# LED_Matrix_3_3_Power.net
KiCad netlist of a schematic drawn in EAGLE
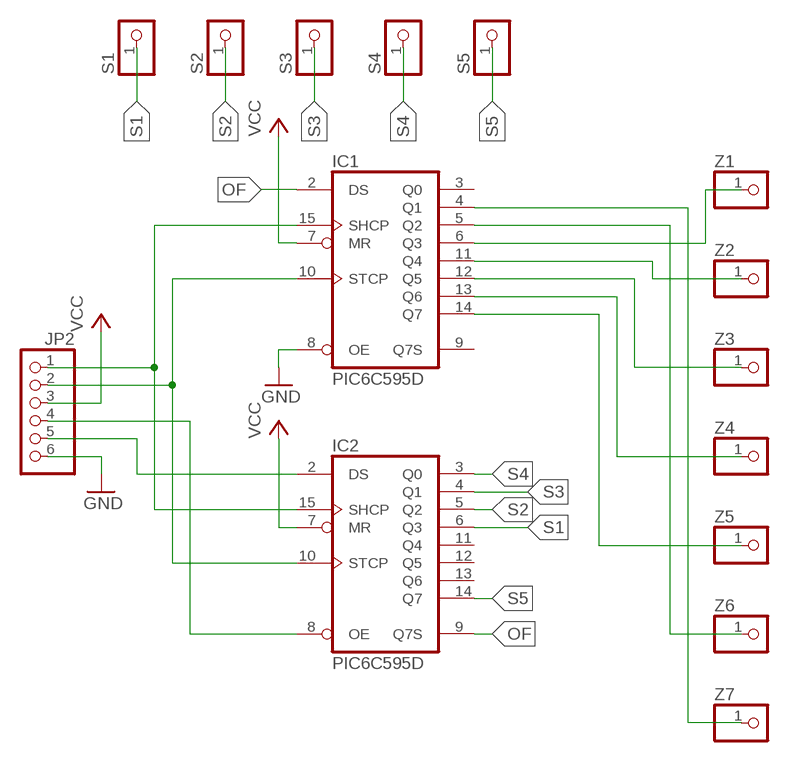
[diagram p0: schematic, sheet 1]

(export (version "E")
  (design (tool "Eeschema 10.0.6"))
  (components
    (comp (ref "IC1")
      (value "PIC6C595D")
      (footprint "eagle-import:SO16")
      (libsource (lib "eagle-import") (part "PIC6C595D"))
    )
    (comp (ref "IC2")
      (value "PIC6C595D")
      (footprint "eagle-import:SO16")
      (libsource (lib "eagle-import") (part "PIC6C595D"))
    )
    (comp (ref "JP2")
      (value "PINHD-1X6")
      (footprint "eagle-import:1X06")
      (libsource (lib "eagle-import") (part "PINHD-1X6"))
    )
    (comp (ref "S1")
      (value "PINHD-1X1")
      (footprint "eagle-import:1X01")
      (libsource (lib "eagle-import") (part "PINHD-1X1"))
    )
    (comp (ref "S2")
      (value "PINHD-1X1")
      (footprint "eagle-import:1X01")
      (libsource (lib "eagle-import") (part "PINHD-1X1"))
    )
    (comp (ref "S3")
      (value "PINHD-1X1")
      (footprint "eagle-import:1X01")
      (libsource (lib "eagle-import") (part "PINHD-1X1"))
    )
    (comp (ref "S4")
      (value "PINHD-1X1")
      (footprint "eagle-import:1X01")
      (libsource (lib "eagle-import") (part "PINHD-1X1"))
    )
    (comp (ref "S5")
      (value "PINHD-1X1")
      (footprint "eagle-import:1X01")
      (libsource (lib "eagle-import") (part "PINHD-1X1"))
    )
    (comp (ref "Z1")
      (value "PINHD-1X1")
      (footprint "eagle-import:1X01")
      (libsource (lib "eagle-import") (part "PINHD-1X1"))
    )
    (comp (ref "Z2")
      (value "PINHD-1X1")
      (footprint "eagle-import:1X01")
      (libsource (lib "eagle-import") (part "PINHD-1X1"))
    )
    (comp (ref "Z3")
      (value "PINHD-1X1")
      (footprint "eagle-import:1X01")
      (libsource (lib "eagle-import") (part "PINHD-1X1"))
    )
    (comp (ref "Z4")
      (value "PINHD-1X1")
      (footprint "eagle-import:1X01")
      (libsource (lib "eagle-import") (part "PINHD-1X1"))
    )
    (comp (ref "Z5")
      (value "PINHD-1X1")
      (footprint "eagle-import:1X01")
      (libsource (lib "eagle-import") (part "PINHD-1X1"))
    )
    (comp (ref "Z6")
      (value "PINHD-1X1")
      (footprint "eagle-import:1X01")
      (libsource (lib "eagle-import") (part "PINHD-1X1"))
    )
    (comp (ref "Z7")
      (value "PINHD-1X1")
      (footprint "eagle-import:1X01")
      (libsource (lib "eagle-import") (part "PINHD-1X1"))
    )
  )
  (nets
    (net (code "1") (name "GND") (class "Default")
      (node (ref "IC1") (pin "8") (pinfunction "OE_8") (pintype "input"))
      (node (ref "JP2") (pin "6") (pinfunction "6_6") (pintype "passive"))
    )
    (net (code "2") (name "Net-(IC1A-Q1)") (class "Default")
      (node (ref "IC1") (pin "4") (pinfunction "Q1_4") (pintype "tri_state"))
      (node (ref "Z7") (pin "1") (pinfunction "1_1") (pintype "passive"))
    )
    (net (code "3") (name "Net-(IC1A-Q2)") (class "Default")
      (node (ref "IC1") (pin "5") (pinfunction "Q2_5") (pintype "tri_state"))
      (node (ref "Z6") (pin "1") (pinfunction "1_1") (pintype "passive"))
    )
    (net (code "4") (name "Net-(IC1A-Q3)") (class "Default")
      (node (ref "IC1") (pin "6") (pinfunction "Q3_6") (pintype "tri_state"))
      (node (ref "Z1") (pin "1") (pinfunction "1_1") (pintype "passive"))
    )
    (net (code "5") (name "Net-(IC1A-Q4)") (class "Default")
      (node (ref "IC1") (pin "11") (pinfunction "Q4_11") (pintype "tri_state"))
      (node (ref "Z2") (pin "1") (pinfunction "1_1") (pintype "passive"))
    )
    (net (code "6") (name "Net-(IC1A-Q5)") (class "Default")
      (node (ref "IC1") (pin "12") (pinfunction "Q5_12") (pintype "tri_state"))
      (node (ref "Z3") (pin "1") (pinfunction "1_1") (pintype "passive"))
    )
    (net (code "7") (name "Net-(IC1A-Q6)") (class "Default")
      (node (ref "IC1") (pin "13") (pinfunction "Q6_13") (pintype "tri_state"))
      (node (ref "Z4") (pin "1") (pinfunction "1_1") (pintype "passive"))
    )
    (net (code "8") (name "Net-(IC1A-Q7)") (class "Default")
      (node (ref "IC1") (pin "14") (pinfunction "Q7_14") (pintype "tri_state"))
      (node (ref "Z5") (pin "1") (pinfunction "1_1") (pintype "passive"))
    )
    (net (code "9") (name "Net-(IC1A-SHCP)") (class "Default")
      (node (ref "IC1") (pin "15") (pinfunction "SHCP_15") (pintype "input"))
      (node (ref "IC2") (pin "15") (pinfunction "SHCP_15") (pintype "input"))
      (node (ref "JP2") (pin "1") (pinfunction "1_1") (pintype "passive"))
    )
    (net (code "10") (name "Net-(IC1A-STCP)") (class "Default")
      (node (ref "IC1") (pin "10") (pinfunction "STCP_10") (pintype "input"))
      (node (ref "IC2") (pin "10") (pinfunction "STCP_10") (pintype "input"))
      (node (ref "JP2") (pin "2") (pinfunction "2_2") (pintype "passive"))
    )
    (net (code "11") (name "Net-(IC2A-DS)") (class "Default")
      (node (ref "IC2") (pin "2") (pinfunction "DS_2") (pintype "input"))
      (node (ref "JP2") (pin "5") (pinfunction "5_5") (pintype "passive"))
    )
    (net (code "12") (name "Net-(IC2A-OE)") (class "Default")
      (node (ref "IC2") (pin "8") (pinfunction "OE_8") (pintype "input"))
      (node (ref "JP2") (pin "4") (pinfunction "4_4") (pintype "passive"))
    )
    (net (code "13") (name "OF") (class "Default")
      (node (ref "IC1") (pin "2") (pinfunction "DS_2") (pintype "input"))
      (node (ref "IC2") (pin "9") (pinfunction "Q7S_9") (pintype "tri_state"))
    )
    (net (code "14") (name "S1") (class "Default")
      (node (ref "IC2") (pin "6") (pinfunction "Q3_6") (pintype "tri_state"))
      (node (ref "S1") (pin "1") (pinfunction "1_1") (pintype "passive"))
    )
    (net (code "15") (name "S2") (class "Default")
      (node (ref "IC2") (pin "5") (pinfunction "Q2_5") (pintype "tri_state"))
      (node (ref "S2") (pin "1") (pinfunction "1_1") (pintype "passive"))
    )
    (net (code "16") (name "S3") (class "Default")
      (node (ref "IC2") (pin "4") (pinfunction "Q1_4") (pintype "tri_state"))
      (node (ref "S3") (pin "1") (pinfunction "1_1") (pintype "passive"))
    )
    (net (code "17") (name "S4") (class "Default")
      (node (ref "IC2") (pin "3") (pinfunction "Q0_3") (pintype "tri_state"))
      (node (ref "S4") (pin "1") (pinfunction "1_1") (pintype "passive"))
    )
    (net (code "18") (name "S5") (class "Default")
      (node (ref "IC2") (pin "14") (pinfunction "Q7_14") (pintype "tri_state"))
      (node (ref "S5") (pin "1") (pinfunction "1_1") (pintype "passive"))
    )
    (net (code "19") (name "VCC") (class "Default")
      (node (ref "IC1") (pin "7") (pinfunction "MR_7") (pintype "input"))
      (node (ref "IC2") (pin "7") (pinfunction "MR_7") (pintype "input"))
      (node (ref "JP2") (pin "3") (pinfunction "3_3") (pintype "passive"))
    )
    (net (code "20") (name "unconnected-(IC1A-Q0-Pad3)") (class "Default")
      (node (ref "IC1") (pin "3") (pinfunction "Q0_3") (pintype "tri_state"))
    )
    (net (code "21") (name "unconnected-(IC1A-Q7S-Pad9)") (class "Default")
      (node (ref "IC1") (pin "9") (pinfunction "Q7S_9") (pintype "tri_state"))
    )
    (net (code "22") (name "unconnected-(IC2A-Q4-Pad11)") (class "Default")
      (node (ref "IC2") (pin "11") (pinfunction "Q4_11") (pintype "tri_state"))
    )
    (net (code "23") (name "unconnected-(IC2A-Q5-Pad12)") (class "Default")
      (node (ref "IC2") (pin "12") (pinfunction "Q5_12") (pintype "tri_state"))
    )
    (net (code "24") (name "unconnected-(IC2A-Q6-Pad13)") (class "Default")
      (node (ref "IC2") (pin "13") (pinfunction "Q6_13") (pintype "tri_state"))
    )
  )
)
